# MSP430FRxxxx.net
KiCad netlist of a schematic drawn in Altium Designer
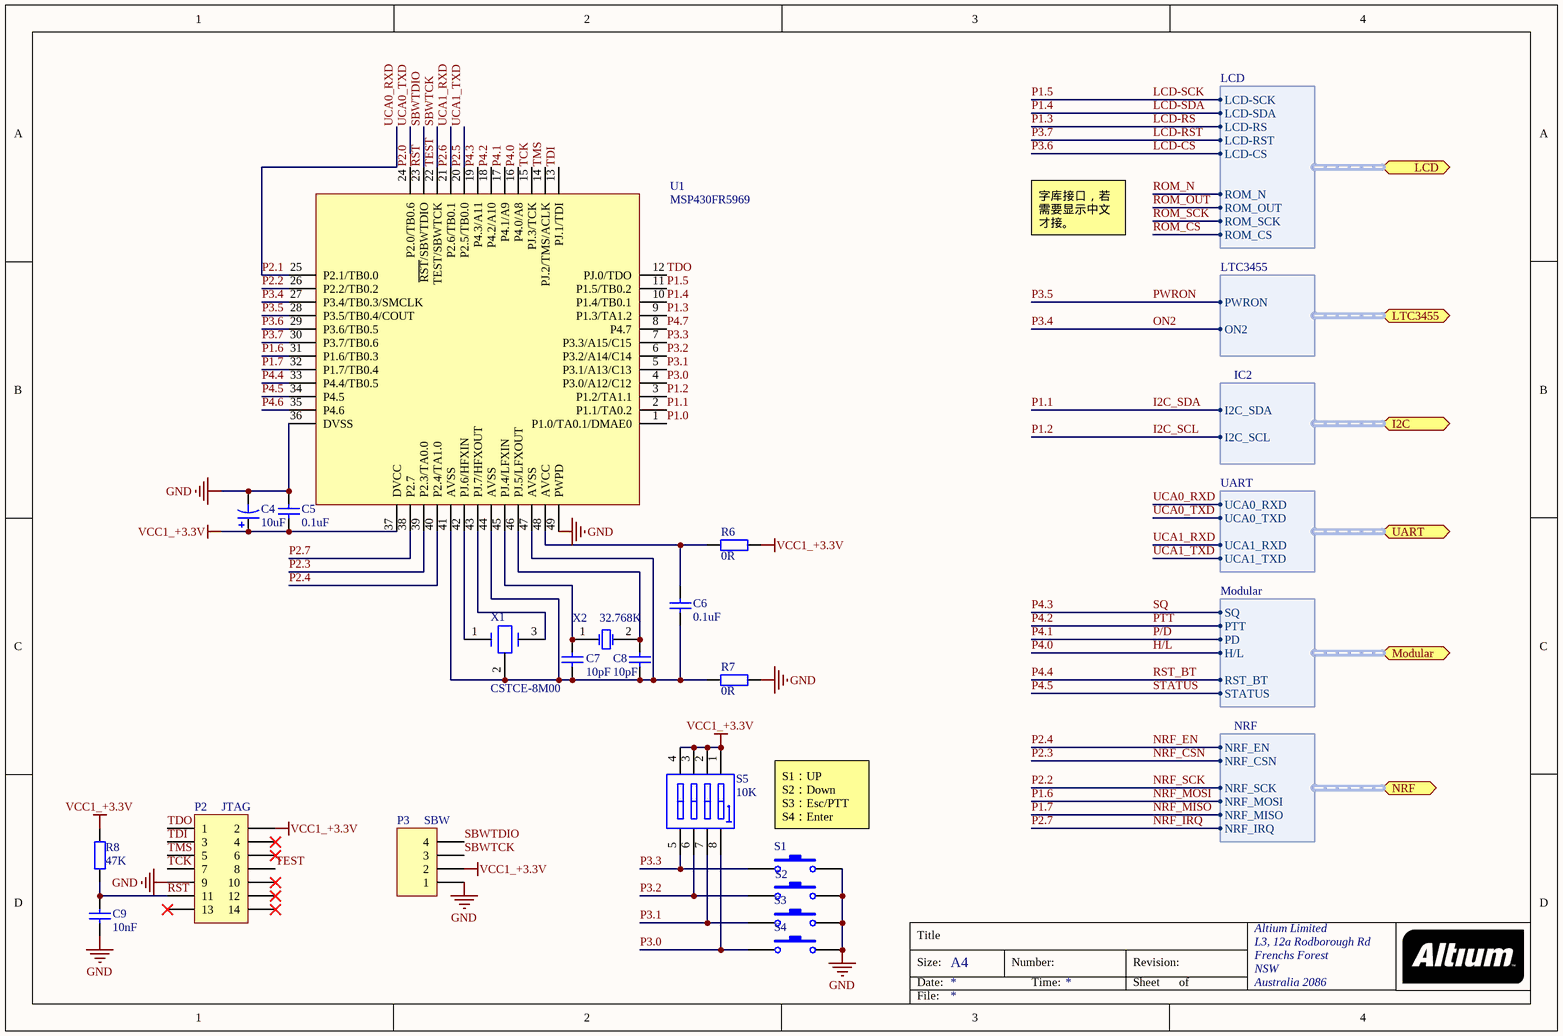
[diagram p0: MSP430FRxxxx.SchDoc]

(export (version "E")
  (design (tool "Eeschema 10.0.6"))
  (components
    (comp (ref "C4")
      (value "10uF")
      (footprint "SMA-C")
      (description "Polarized Capacitor (Radial)")
      (fields (field (name "Comment") "Cap Pol1") (field (name "PUBLISHER") "Altium Limited"))
      (libsource (lib "xxxlzjxxx Devices") (part "Cap Pol1"))
    )
    (comp (ref "C5")
      (value "0.1uF")
      (footprint "C0805")
      (description "Capacitor")
      (fields (field (name "Comment") "Cap") (field (name "PUBLISHER") "Altium Limited"))
      (libsource (lib "xxxlzjxxx Devices") (part "Cap"))
    )
    (comp (ref "C6")
      (value "0.1uF")
      (footprint "C0805")
      (description "Capacitor")
      (fields (field (name "Comment") "Cap") (field (name "PUBLISHER") "Altium Limited"))
      (libsource (lib "xxxlzjxxx Devices") (part "Cap"))
    )
    (comp (ref "C7")
      (value "10pF")
      (footprint "C0805")
      (description "Capacitor")
      (fields (field (name "Comment") "Cap") (field (name "PUBLISHER") "Altium Limited"))
      (libsource (lib "xxxlzjxxx Devices") (part "Cap"))
    )
    (comp (ref "C8")
      (value "10pF")
      (footprint "C0805")
      (description "Capacitor")
      (fields (field (name "Comment") "Cap") (field (name "PUBLISHER") "Altium Limited"))
      (libsource (lib "xxxlzjxxx Devices") (part "Cap"))
    )
    (comp (ref "C9")
      (value "10nF")
      (footprint "C0805")
      (description "Capacitor")
      (fields (field (name "Comment") "Cap") (field (name "PUBLISHER") "Altium Limited"))
      (libsource (lib "xxxlzjxxx Devices") (part "Cap"))
    )
    (comp (ref "P2")
      (value "JTAG")
      (footprint "JTAG")
      (description "Header, 7-Pin, Dual row")
      (fields (field (name "PUBLISHER") "Altium Limited"))
      (libsource (lib "xxxlzjxxx Connectors") (part "Header 7X2"))
    )
    (comp (ref "P3")
      (value "SBW")
      (footprint "HDR1X4")
      (description "Header, 4-Pin")
      (fields (field (name "PUBLISHER") "Altium Limited"))
      (libsource (lib "xxxlzjxxx Connectors") (part "Header 4"))
    )
    (comp (ref "R6")
      (value "0R")
      (footprint "R0805")
      (description "Resistor")
      (fields (field (name "Comment") "Res2") (field (name "PUBLISHER") "Altium Limited"))
      (libsource (lib "xxxlzjxxx Devices") (part "Res2"))
    )
    (comp (ref "R7")
      (value "0R")
      (footprint "R0805")
      (description "Resistor")
      (fields (field (name "Comment") "Res2") (field (name "PUBLISHER") "Altium Limited"))
      (libsource (lib "xxxlzjxxx Devices") (part "Res2"))
    )
    (comp (ref "R8")
      (value "47K")
      (footprint "R0805")
      (description "Resistor")
      (fields (field (name "Comment") "Res2") (field (name "PUBLISHER") "Altium Limited"))
      (libsource (lib "") (part "Res2_1"))
    )
    (comp (ref "S1")
      (value "SW-PB")
      (footprint "SW-SMD1")
      (description "Switch")
      (fields (field (name "PUBLISHER") "Altium Limited"))
      (libsource (lib "xxxlzjxxx Devices") (part "SW-PB"))
    )
    (comp (ref "S2")
      (value "SW-PB")
      (footprint "SW-SMD1")
      (description "Switch")
      (fields (field (name "PUBLISHER") "Altium Limited"))
      (libsource (lib "xxxlzjxxx Devices") (part "SW-PB"))
    )
    (comp (ref "S3")
      (value "SW-PB")
      (footprint "SW-SMD1")
      (description "Switch")
      (fields (field (name "PUBLISHER") "Altium Limited"))
      (libsource (lib "xxxlzjxxx Devices") (part "SW-PB"))
    )
    (comp (ref "S4")
      (value "SW-PB")
      (footprint "SW-SMD1")
      (description "Switch")
      (fields (field (name "PUBLISHER") "Altium Limited"))
      (libsource (lib "xxxlzjxxx Devices") (part "SW-PB"))
    )
    (comp (ref "S5")
      (value "10K")
      (footprint "R0805-4P")
      (description "DIP Switch, 4 Position, SPST")
      (fields (field (name "PUBLISHER") "Altium Limited"))
      (libsource (lib "xxxlzjxxx Devices") (part "SW DIP-4"))
    )
    (comp (ref "U1")
      (value "MSP430FR5969")
      (footprint "QFN-48")
      (description "MSP420FRxxxx")
      (libsource (lib "FR5969v1.0") (part "MSP430FR5969"))
    )
    (comp (ref "X1")
      (value "CSTCE-8M00")
      (footprint "CSTCE-8M00")
      (libsource (lib "MOCOv6.0") (part "CSTCE-8M00"))
    )
    (comp (ref "X2")
      (value "32.768K")
      (footprint "32768")
      (description "Crystal Oscillator")
      (fields (field (name "PUBLISHER") "Altium Limited"))
      (libsource (lib "xxxlzjxxx Devices") (part "XTAL"))
    )
  )
  (nets
    (net (code "7") (name "/H{slash}L") (class "Default")
      (node (ref "U1") (pin "16") (pinfunction "P4.0/A8_16") (pintype "passive"))
    )
    (net (code "8") (name "/I2C_SCL") (class "Default")
      (node (ref "U1") (pin "3") (pinfunction "P1.2/TA1.1_3") (pintype "passive"))
    )
    (net (code "9") (name "/I2C_SDA") (class "Default")
      (node (ref "U1") (pin "2") (pinfunction "P1.1/TA0.2_2") (pintype "passive"))
    )
    (net (code "10") (name "/LCD-CS") (class "Default")
      (node (ref "U1") (pin "29") (pinfunction "P3.6/TB0.5_29") (pintype "passive"))
    )
    (net (code "11") (name "/LCD-RS") (class "Default")
      (node (ref "U1") (pin "9") (pinfunction "P1.3/TA1.2_9") (pintype "passive"))
    )
    (net (code "12") (name "/LCD-RST") (class "Default")
      (node (ref "U1") (pin "30") (pinfunction "P3.7/TB0.6_30") (pintype "passive"))
    )
    (net (code "13") (name "/LCD-SCK") (class "Default")
      (node (ref "U1") (pin "11") (pinfunction "P1.5/TB0.2_11") (pintype "passive"))
    )
    (net (code "14") (name "/LCD-SDA") (class "Default")
      (node (ref "U1") (pin "10") (pinfunction "P1.4/TB0.1_10") (pintype "passive"))
    )
    (net (code "15") (name "/NRF_CSN") (class "Default")
      (node (ref "U1") (pin "39") (pinfunction "P2.3/TA0.0_39") (pintype "passive"))
    )
    (net (code "16") (name "/NRF_EN") (class "Default")
      (node (ref "U1") (pin "40") (pinfunction "P2.4/TA1.0_40") (pintype "passive"))
    )
    (net (code "17") (name "/NRF_IRQ") (class "Default")
      (node (ref "U1") (pin "38") (pinfunction "P2.7_38") (pintype "passive"))
    )
    (net (code "18") (name "/NRF_MISO") (class "Default")
      (node (ref "U1") (pin "32") (pinfunction "P1.7/TB0.4_32") (pintype "passive"))
    )
    (net (code "19") (name "/NRF_MOSI") (class "Default")
      (node (ref "U1") (pin "31") (pinfunction "P1.6/TB0.3_31") (pintype "passive"))
    )
    (net (code "20") (name "/NRF_SCK") (class "Default")
      (node (ref "U1") (pin "26") (pinfunction "P2.2/TB0.2_26") (pintype "passive"))
    )
    (net (code "21") (name "/ON2") (class "Default")
      (node (ref "U1") (pin "27") (pinfunction "P3.4/TB0.3/SMCLK_27") (pintype "passive"))
    )
    (net (code "22") (name "/P1.0") (class "Default")
      (node (ref "U1") (pin "1") (pinfunction "P1.0/TA0.1/DMAE0_1") (pintype "passive"))
    )
    (net (code "23") (name "/P2.0") (class "Default")
      (node (ref "U1") (pin "24") (pinfunction "P2.0/TB0.6_24") (pintype "passive"))
    )
    (net (code "24") (name "/P2.1") (class "Default")
      (node (ref "U1") (pin "25") (pinfunction "P2.1/TB0.0_25") (pintype "passive"))
    )
    (net (code "25") (name "/P2.5") (class "Default")
      (node (ref "U1") (pin "20") (pinfunction "P2.5/TB0.0_20") (pintype "passive"))
    )
    (net (code "26") (name "/P2.6") (class "Default")
      (node (ref "U1") (pin "21") (pinfunction "P2.6/TB0.1_21") (pintype "passive"))
    )
    (net (code "27") (name "/P3.0") (class "Default")
      (node (ref "S4") (pin "1") (pinfunction "1_1") (pintype "passive"))
      (node (ref "S5") (pin "8") (pinfunction "B1_8") (pintype "passive"))
      (node (ref "U1") (pin "4") (pinfunction "P3.0/A12/C12_4") (pintype "passive"))
    )
    (net (code "28") (name "/P3.1") (class "Default")
      (node (ref "S3") (pin "1") (pinfunction "1_1") (pintype "passive"))
      (node (ref "S5") (pin "7") (pinfunction "B2_7") (pintype "passive"))
      (node (ref "U1") (pin "5") (pinfunction "P3.1/A13/C13_5") (pintype "passive"))
    )
    (net (code "29") (name "/P3.2") (class "Default")
      (node (ref "S2") (pin "1") (pinfunction "1_1") (pintype "passive"))
      (node (ref "S5") (pin "6") (pinfunction "B3_6") (pintype "passive"))
      (node (ref "U1") (pin "6") (pinfunction "P3.2/A14/C14_6") (pintype "passive"))
    )
    (net (code "30") (name "/P3.3") (class "Default")
      (node (ref "S1") (pin "1") (pinfunction "1_1") (pintype "passive"))
      (node (ref "S5") (pin "5") (pinfunction "B4_5") (pintype "passive"))
      (node (ref "U1") (pin "7") (pinfunction "P3.3/A15/C15_7") (pintype "passive"))
    )
    (net (code "31") (name "/P3.5") (class "Default")
      (node (ref "U1") (pin "28") (pinfunction "P3.5/TB0.4/COUT_28") (pintype "passive"))
    )
    (net (code "32") (name "/P4.1") (class "Default")
      (node (ref "U1") (pin "17") (pinfunction "P4.1/A9_17") (pintype "passive"))
    )
    (net (code "33") (name "/P4.2") (class "Default")
      (node (ref "U1") (pin "18") (pinfunction "P4.2/A10_18") (pintype "passive"))
    )
    (net (code "34") (name "/P4.3") (class "Default")
      (node (ref "U1") (pin "19") (pinfunction "P4.3/A11_19") (pintype "passive"))
    )
    (net (code "35") (name "/P4.4") (class "Default")
      (node (ref "U1") (pin "33") (pinfunction "P4.4/TB0.5_33") (pintype "passive"))
    )
    (net (code "36") (name "/P4.5") (class "Default")
      (node (ref "U1") (pin "34") (pinfunction "P4.5_34") (pintype "passive"))
    )
    (net (code "37") (name "/P4.6") (class "Default")
      (node (ref "U1") (pin "35") (pinfunction "P4.6_35") (pintype "passive"))
    )
    (net (code "38") (name "/P4.7") (class "Default")
      (node (ref "U1") (pin "8") (pinfunction "P4.7_8") (pintype "passive"))
    )
    (net (code "43") (name "/SBWTCK") (class "Default")
      (node (ref "P2") (pin "8") (pinfunction "8_8") (pintype "passive"))
      (node (ref "P3") (pin "3") (pinfunction "3_3") (pintype "passive"))
      (node (ref "U1") (pin "22") (pinfunction "TEST/SBWTCK_22") (pintype "passive"))
    )
    (net (code "44") (name "/SBWTDIO") (class "Default")
      (node (ref "C9") (pin "1") (pinfunction "1_1") (pintype "passive"))
      (node (ref "P2") (pin "11") (pinfunction "11_11") (pintype "passive"))
      (node (ref "P3") (pin "4") (pinfunction "4_4") (pintype "passive"))
      (node (ref "R8") (pin "1") (pinfunction "1_1") (pintype "passive"))
      (node (ref "U1") (pin "23") (pinfunction "~{RST}/SBWTDIO_23") (pintype "passive"))
    )
    (net (code "45") (name "/TCK") (class "Default")
      (node (ref "P2") (pin "7") (pinfunction "7_7") (pintype "passive"))
      (node (ref "U1") (pin "15") (pinfunction "PJ.3/TCK_15") (pintype "passive"))
    )
    (net (code "46") (name "/TDI") (class "Default")
      (node (ref "P2") (pin "3") (pinfunction "3_3") (pintype "passive"))
      (node (ref "U1") (pin "13") (pinfunction "PJ.1/TDI_13") (pintype "passive"))
    )
    (net (code "47") (name "/TDO") (class "Default")
      (node (ref "P2") (pin "1") (pinfunction "1_1") (pintype "passive"))
      (node (ref "U1") (pin "12") (pinfunction "PJ.0/TDO_12") (pintype "passive"))
    )
    (net (code "48") (name "/TMS") (class "Default")
      (node (ref "P2") (pin "5") (pinfunction "5_5") (pintype "passive"))
      (node (ref "U1") (pin "14") (pinfunction "PJ.2/TMS/ACLK_14") (pintype "passive"))
    )
    (net (code "56") (name "GND") (class "Default")
      (node (ref "C4") (pin "2") (pinfunction "2_2") (pintype "passive"))
      (node (ref "C5") (pin "1") (pinfunction "1_1") (pintype "passive"))
      (node (ref "C9") (pin "2") (pinfunction "2_2") (pintype "passive"))
      (node (ref "P2") (pin "9") (pinfunction "9_9") (pintype "passive"))
      (node (ref "P3") (pin "1") (pinfunction "1_1") (pintype "passive"))
      (node (ref "R7") (pin "2") (pinfunction "2_2") (pintype "passive"))
      (node (ref "S1") (pin "2") (pinfunction "2_2") (pintype "passive"))
      (node (ref "S2") (pin "2") (pinfunction "2_2") (pintype "passive"))
      (node (ref "S3") (pin "2") (pinfunction "2_2") (pintype "passive"))
      (node (ref "S4") (pin "2") (pinfunction "2_2") (pintype "passive"))
      (node (ref "U1") (pin "36") (pinfunction "DVSS_36") (pintype "passive"))
      (node (ref "U1") (pin "49") (pinfunction "PWPD_49") (pintype "passive"))
    )
    (net (code "57") (name "Net-(C6-Pad2)") (class "Default")
      (node (ref "C6") (pin "2") (pinfunction "2_2") (pintype "passive"))
      (node (ref "C7") (pin "1") (pinfunction "1_1") (pintype "passive"))
      (node (ref "C8") (pin "1") (pinfunction "1_1") (pintype "passive"))
      (node (ref "R7") (pin "1") (pinfunction "1_1") (pintype "passive"))
      (node (ref "U1") (pin "41") (pinfunction "AVSS_41") (pintype "passive"))
      (node (ref "U1") (pin "44") (pinfunction "AVSS_44") (pintype "passive"))
      (node (ref "U1") (pin "47") (pinfunction "AVSS_47") (pintype "passive"))
      (node (ref "X1") (pin "2") (pinfunction "2_2") (pintype "passive"))
    )
    (net (code "58") (name "Net-(U1-AVCC)") (class "Default")
      (node (ref "C6") (pin "1") (pinfunction "1_1") (pintype "passive"))
      (node (ref "R6") (pin "1") (pinfunction "1_1") (pintype "passive"))
      (node (ref "U1") (pin "48") (pinfunction "AVCC_48") (pintype "passive"))
    )
    (net (code "59") (name "Net-(U1-PJ.4{slash}LFXIN)") (class "Default")
      (node (ref "C7") (pin "2") (pinfunction "2_2") (pintype "passive"))
      (node (ref "U1") (pin "45") (pinfunction "PJ.4/LFXIN_45") (pintype "passive"))
      (node (ref "X2") (pin "1") (pinfunction "OSC1_1") (pintype "passive"))
    )
    (net (code "60") (name "Net-(U1-PJ.5{slash}LFXOUT)") (class "Default")
      (node (ref "C8") (pin "2") (pinfunction "2_2") (pintype "passive"))
      (node (ref "U1") (pin "46") (pinfunction "PJ.5/LFXOUT_46") (pintype "passive"))
      (node (ref "X2") (pin "2") (pinfunction "OSC2_2") (pintype "passive"))
    )
    (net (code "61") (name "Net-(U1-PJ.6{slash}HFXIN)") (class "Default")
      (node (ref "U1") (pin "42") (pinfunction "PJ.6/HFXIN_42") (pintype "passive"))
      (node (ref "X1") (pin "1") (pinfunction "1_1") (pintype "passive"))
    )
    (net (code "62") (name "Net-(U1-PJ.7{slash}HFXOUT)") (class "Default")
      (node (ref "U1") (pin "43") (pinfunction "PJ.7/HFXOUT_43") (pintype "passive"))
      (node (ref "X1") (pin "3") (pinfunction "3_3") (pintype "passive"))
    )
    (net (code "63") (name "VCC1_+3.3V") (class "Default")
      (node (ref "C4") (pin "1") (pinfunction "1_1") (pintype "passive"))
      (node (ref "C5") (pin "2") (pinfunction "2_2") (pintype "passive"))
      (node (ref "P2") (pin "2") (pinfunction "2_2") (pintype "passive"))
      (node (ref "P3") (pin "2") (pinfunction "2_2") (pintype "passive"))
      (node (ref "R6") (pin "2") (pinfunction "2_2") (pintype "passive"))
      (node (ref "R8") (pin "2") (pinfunction "2_2") (pintype "passive"))
      (node (ref "S5") (pin "1") (pinfunction "A1_1") (pintype "passive"))
      (node (ref "S5") (pin "2") (pinfunction "A2_2") (pintype "passive"))
      (node (ref "S5") (pin "3") (pinfunction "A3_3") (pintype "passive"))
      (node (ref "S5") (pin "4") (pinfunction "A4_4") (pintype "passive"))
      (node (ref "U1") (pin "37") (pinfunction "DVCC_37") (pintype "passive"))
    )
    (net (code "64") (name "unconnected-(P2-Pad4)") (class "Default")
      (node (ref "P2") (pin "4") (pinfunction "4_4") (pintype "passive+no_connect"))
    )
    (net (code "65") (name "unconnected-(P2-Pad6)") (class "Default")
      (node (ref "P2") (pin "6") (pinfunction "6_6") (pintype "passive+no_connect"))
    )
    (net (code "66") (name "unconnected-(P2-Pad10)") (class "Default")
      (node (ref "P2") (pin "10") (pinfunction "10_10") (pintype "passive+no_connect"))
    )
    (net (code "67") (name "unconnected-(P2-Pad12)") (class "Default")
      (node (ref "P2") (pin "12") (pinfunction "12_12") (pintype "passive+no_connect"))
    )
    (net (code "68") (name "unconnected-(P2-Pad13)") (class "Default")
      (node (ref "P2") (pin "13") (pinfunction "13_13") (pintype "passive+no_connect"))
    )
    (net (code "69") (name "unconnected-(P2-Pad14)") (class "Default")
      (node (ref "P2") (pin "14") (pinfunction "14_14") (pintype "passive+no_connect"))
    )
  )
)
